# I_O.net
KiCad netlist of a schematic drawn in Altium Designer
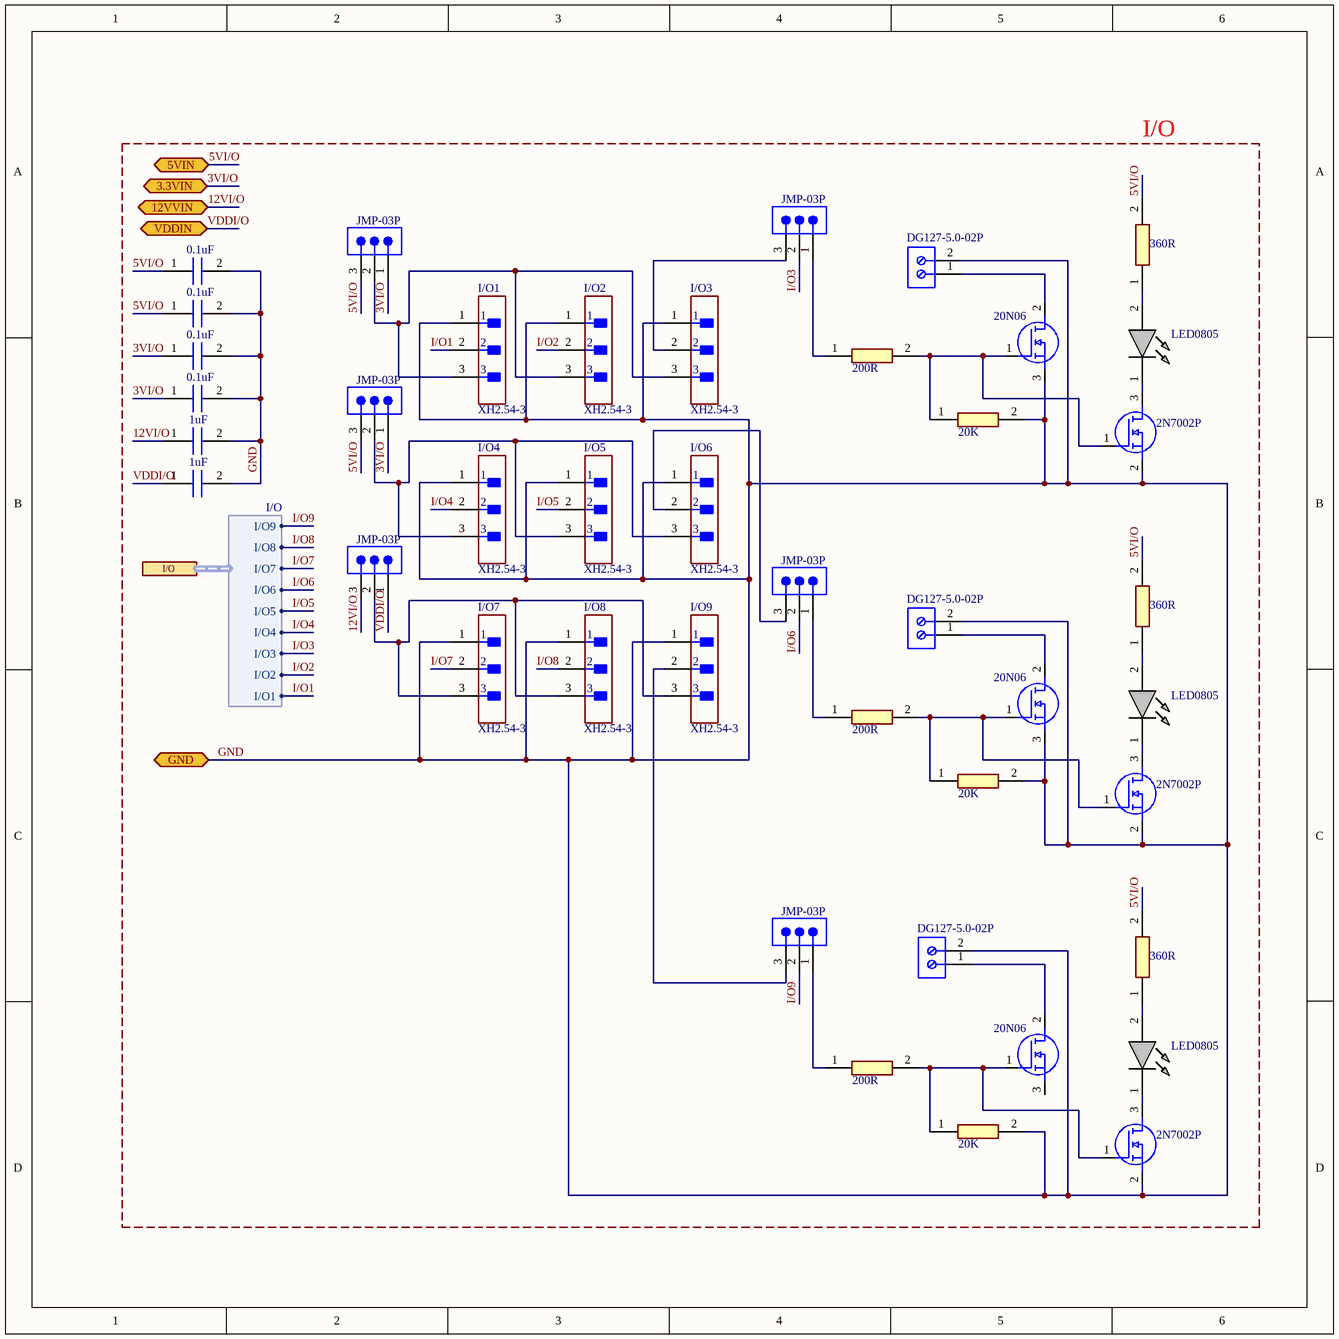
[diagram p0: I_O.SchDoc]

(export (version "E")
  (design (tool "Eeschema 10.0.6"))
  (components
    (comp (ref "CAP3VI/O1")
      (value "0.1uF")
      (footprint "CAP0805")
      (description "CAP-SMD0805")
      (libsource (lib "Components_Robots") (part "CAP0805"))
    )
    (comp (ref "CAP3VI/O2")
      (value "0.1uF")
      (footprint "CAP0805")
      (description "CAP-SMD0805")
      (libsource (lib "Components_Robots") (part "CAP0805"))
    )
    (comp (ref "CAP5VI/O1")
      (value "0.1uF")
      (footprint "CAP0805")
      (description "CAP-SMD0805")
      (libsource (lib "Components_Robots") (part "CAP0805"))
    )
    (comp (ref "CAP5VI/O2")
      (value "0.1uF")
      (footprint "CAP0805")
      (description "CAP-SMD0805")
      (libsource (lib "Components_Robots") (part "CAP0805"))
    )
    (comp (ref "CAP12VI/O")
      (value "1uF")
      (footprint "К10-17Б")
      (description "К10-17Б")
      (libsource (lib "Components_Robots") (part "CAP"))
    )
    (comp (ref "CAPVDDI/O")
      (value "1uF")
      (footprint "К10-17Б")
      (description "К10-17Б")
      (libsource (lib "Components_Robots") (part "CAP"))
    )
    (comp (ref "I/O1")
      (value "XH2.54-3")
      (footprint "XH2.54-3")
      (description "JST XH2.54-3pin")
      (libsource (lib "Components_Robots") (part "XH2.54-3"))
    )
    (comp (ref "I/O2")
      (value "XH2.54-3")
      (footprint "XH2.54-3")
      (description "JST XH2.54-3pin")
      (libsource (lib "Components_Robots") (part "XH2.54-3"))
    )
    (comp (ref "I/O3")
      (value "XH2.54-3")
      (footprint "XH2.54-3")
      (description "JST XH2.54-3pin")
      (libsource (lib "Components_Robots") (part "XH2.54-3"))
    )
    (comp (ref "I/O4")
      (value "XH2.54-3")
      (footprint "XH2.54-3")
      (description "JST XH2.54-3pin")
      (libsource (lib "Components_Robots") (part "XH2.54-3"))
    )
    (comp (ref "I/O5")
      (value "XH2.54-3")
      (footprint "XH2.54-3")
      (description "JST XH2.54-3pin")
      (libsource (lib "Components_Robots") (part "XH2.54-3"))
    )
    (comp (ref "I/O6")
      (value "XH2.54-3")
      (footprint "XH2.54-3")
      (description "JST XH2.54-3pin")
      (libsource (lib "Components_Robots") (part "XH2.54-3"))
    )
    (comp (ref "I/O7")
      (value "XH2.54-3")
      (footprint "XH2.54-3")
      (description "JST XH2.54-3pin")
      (libsource (lib "Components_Robots") (part "XH2.54-3"))
    )
    (comp (ref "I/O8")
      (value "XH2.54-3")
      (footprint "XH2.54-3")
      (description "JST XH2.54-3pin")
      (libsource (lib "Components_Robots") (part "XH2.54-3"))
    )
    (comp (ref "I/O9")
      (value "XH2.54-3")
      (footprint "XH2.54-3")
      (description "JST XH2.54-3pin")
      (libsource (lib "Components_Robots") (part "XH2.54-3"))
    )
    (comp (ref "JMPI/O1")
      (value "JMP-03P")
      (footprint "JMP-03P")
      (description "PLS-1x3")
      (libsource (lib "Components_Robots") (part "JMP-03P"))
    )
    (comp (ref "JMPI/O2")
      (value "JMP-03P")
      (footprint "JMP-03P")
      (description "PLS-1x3")
      (libsource (lib "Components_Robots") (part "JMP-03P"))
    )
    (comp (ref "JMPI/O3")
      (value "JMP-03P")
      (footprint "JMP-03P")
      (description "PLS-1x3")
      (libsource (lib "Components_Robots") (part "JMP-03P"))
    )
    (comp (ref "JMPI/O3HIGH")
      (value "JMP-03P")
      (footprint "JMP-03P")
      (description "PLS-1x3")
      (libsource (lib "Components_Robots") (part "JMP-03P"))
    )
    (comp (ref "JMPI/O6")
      (value "JMP-03P")
      (footprint "JMP-03P")
      (description "PLS-1x3")
      (libsource (lib "Components_Robots") (part "JMP-03P"))
    )
    (comp (ref "JMPI/O9")
      (value "JMP-03P")
      (footprint "JMP-03P")
      (description "PLS-1x3")
      (libsource (lib "Components_Robots") (part "JMP-03P"))
    )
    (comp (ref "LED3(GREEN)")
      (value "LED0805")
      (footprint "LED0805")
      (description "LED-SMD0805")
      (libsource (lib "Components_Robots") (part "LED0805"))
    )
    (comp (ref "LED6(GREEN)")
      (value "LED0805")
      (footprint "LED0805")
      (description "LED-SMD0805")
      (libsource (lib "Components_Robots") (part "LED0805"))
    )
    (comp (ref "LED9(GREEN)")
      (value "LED0805")
      (footprint "LED0805")
      (description "LED-SMD0805")
      (libsource (lib "Components_Robots") (part "LED0805"))
    )
    (comp (ref "M1")
      (value "2N7002P")
      (footprint "2N7002P")
      (description "2N7002P,215")
      (libsource (lib "Components_Robots") (part "2N7002P"))
    )
    (comp (ref "M6")
      (value "2N7002P")
      (footprint "2N7002P")
      (description "2N7002P,215")
      (libsource (lib "Components_Robots") (part "2N7002P"))
    )
    (comp (ref "M9")
      (value "2N7002P")
      (footprint "2N7002P")
      (description "2N7002P,215")
      (libsource (lib "Components_Robots") (part "2N7002P"))
    )
    (comp (ref "MS1")
      (value "20N06")
      (footprint "20N06")
      (description "NMOSFET-20N06")
      (libsource (lib "Components_Robots") (part "20N06"))
    )
    (comp (ref "MS6")
      (value "20N06")
      (footprint "20N06")
      (description "NMOSFET-20N06")
      (libsource (lib "Components_Robots") (part "20N06"))
    )
    (comp (ref "MS9")
      (value "20N06")
      (footprint "20N06")
      (description "NMOSFET-20N06")
      (libsource (lib "Components_Robots") (part "20N06"))
    )
    (comp (ref "OUT3")
      (value "DG127-5.0-02P")
      (footprint "DG127-5.0-02P")
      (description "DG127-5.0-02P-14-00Z")
      (libsource (lib "Components_Robots") (part "DG127-5.0-02P"))
    )
    (comp (ref "OUT6")
      (value "DG127-5.0-02P")
      (footprint "DG127-5.0-02P")
      (description "DG127-5.0-02P-14-00Z")
      (libsource (lib "Components_Robots") (part "DG127-5.0-02P"))
    )
    (comp (ref "OUT9")
      (value "DG127-5.0-02P")
      (footprint "DG127-5.0-02P")
      (description "DG127-5.0-02P-14-00Z")
      (libsource (lib "Components_Robots") (part "DG127-5.0-02P"))
    )
    (comp (ref "RES1")
      (value "200R")
      (footprint "RES0805")
      (description "RES-SMD0805")
      (libsource (lib "Components_Robots") (part "RES0805"))
    )
    (comp (ref "RES2")
      (value "20K")
      (footprint "RES0805")
      (description "RES-SMD0805")
      (libsource (lib "Components_Robots") (part "RES0805"))
    )
    (comp (ref "RES3")
      (value "360R")
      (footprint "RES0805")
      (description "RES-SMD0805")
      (libsource (lib "") (part "RES0805_1"))
    )
    (comp (ref "RES4")
      (value "200R")
      (footprint "RES0805")
      (description "RES-SMD0805")
      (libsource (lib "Components_Robots") (part "RES0805"))
    )
    (comp (ref "RES5")
      (value "20K")
      (footprint "RES0805")
      (description "RES-SMD0805")
      (libsource (lib "Components_Robots") (part "RES0805"))
    )
    (comp (ref "RES6")
      (value "360R")
      (footprint "RES0805")
      (description "RES-SMD0805")
      (libsource (lib "") (part "RES0805_1"))
    )
    (comp (ref "RES7")
      (value "200R")
      (footprint "RES0805")
      (description "RES-SMD0805")
      (libsource (lib "Components_Robots") (part "RES0805"))
    )
    (comp (ref "RES8")
      (value "20K")
      (footprint "RES0805")
      (description "RES-SMD0805")
      (libsource (lib "Components_Robots") (part "RES0805"))
    )
    (comp (ref "RES9")
      (value "360R")
      (footprint "RES0805")
      (description "RES-SMD0805")
      (libsource (lib "") (part "RES0805_1"))
    )
  )
  (nets
    (net (code "2") (name "/3VI{slash}O") (class "Default")
      (node (ref "CAP3VI/O1") (pin "1") (pinfunction "1_1") (pintype "passive"))
      (node (ref "CAP3VI/O2") (pin "1") (pinfunction "1_1") (pintype "passive"))
      (node (ref "JMPI/O1") (pin "1") (pinfunction "1_1") (pintype "passive"))
      (node (ref "JMPI/O2") (pin "1") (pinfunction "1_1") (pintype "passive"))
    )
    (net (code "3") (name "/5VI{slash}O") (class "Default")
      (node (ref "CAP5VI/O1") (pin "1") (pinfunction "1_1") (pintype "passive"))
      (node (ref "CAP5VI/O2") (pin "1") (pinfunction "1_1") (pintype "passive"))
      (node (ref "JMPI/O1") (pin "3") (pinfunction "3_3") (pintype "passive"))
      (node (ref "JMPI/O2") (pin "3") (pinfunction "3_3") (pintype "passive"))
      (node (ref "RES3") (pin "2") (pinfunction "2_2") (pintype "passive"))
      (node (ref "RES6") (pin "2") (pinfunction "2_2") (pintype "passive"))
      (node (ref "RES9") (pin "2") (pinfunction "2_2") (pintype "passive"))
    )
    (net (code "4") (name "/12VI{slash}O") (class "Default")
      (node (ref "CAP12VI/O") (pin "1") (pinfunction "1_1") (pintype "passive"))
      (node (ref "JMPI/O3") (pin "3") (pinfunction "3_3") (pintype "passive"))
    )
    (net (code "5") (name "/GND") (class "Default")
      (node (ref "CAP12VI/O") (pin "2") (pinfunction "2_2") (pintype "passive"))
      (node (ref "CAP3VI/O1") (pin "2") (pinfunction "2_2") (pintype "passive"))
      (node (ref "CAP3VI/O2") (pin "2") (pinfunction "2_2") (pintype "passive"))
      (node (ref "CAP5VI/O1") (pin "2") (pinfunction "2_2") (pintype "passive"))
      (node (ref "CAP5VI/O2") (pin "2") (pinfunction "2_2") (pintype "passive"))
      (node (ref "CAPVDDI/O") (pin "2") (pinfunction "2_2") (pintype "passive"))
      (node (ref "I/O1") (pin "1") (pinfunction "1_1") (pintype "passive"))
      (node (ref "I/O2") (pin "1") (pinfunction "1_1") (pintype "passive"))
      (node (ref "I/O3") (pin "1") (pinfunction "1_1") (pintype "passive"))
      (node (ref "I/O4") (pin "1") (pinfunction "1_1") (pintype "passive"))
      (node (ref "I/O5") (pin "1") (pinfunction "1_1") (pintype "passive"))
      (node (ref "I/O6") (pin "1") (pinfunction "1_1") (pintype "passive"))
      (node (ref "I/O7") (pin "1") (pinfunction "1_1") (pintype "passive"))
      (node (ref "I/O8") (pin "1") (pinfunction "1_1") (pintype "passive"))
      (node (ref "I/O9") (pin "1") (pinfunction "1_1") (pintype "passive"))
      (node (ref "M1") (pin "2") (pinfunction "S_2") (pintype "passive"))
      (node (ref "M6") (pin "2") (pinfunction "S_2") (pintype "passive"))
      (node (ref "M9") (pin "2") (pinfunction "S_2") (pintype "passive"))
      (node (ref "MS1") (pin "3") (pinfunction "S_3") (pintype "passive"))
      (node (ref "MS6") (pin "3") (pinfunction "S_3") (pintype "passive"))
      (node (ref "OUT3") (pin "2") (pinfunction "2_2") (pintype "passive"))
      (node (ref "OUT6") (pin "2") (pinfunction "2_2") (pintype "passive"))
      (node (ref "OUT9") (pin "2") (pinfunction "2_2") (pintype "passive"))
      (node (ref "RES2") (pin "2") (pinfunction "2_2") (pintype "passive"))
      (node (ref "RES5") (pin "2") (pinfunction "2_2") (pintype "passive"))
      (node (ref "RES8") (pin "2") (pinfunction "2_2") (pintype "passive"))
    )
    (net (code "6") (name "/I{slash}O1") (class "Default")
      (node (ref "I/O1") (pin "2") (pinfunction "2_2") (pintype "passive"))
    )
    (net (code "7") (name "/I{slash}O2") (class "Default")
      (node (ref "I/O2") (pin "2") (pinfunction "2_2") (pintype "passive"))
    )
    (net (code "8") (name "/I{slash}O3") (class "Default")
      (node (ref "JMPI/O3HIGH") (pin "2") (pinfunction "2_2") (pintype "passive"))
    )
    (net (code "9") (name "/I{slash}O4") (class "Default")
      (node (ref "I/O4") (pin "2") (pinfunction "2_2") (pintype "passive"))
    )
    (net (code "10") (name "/I{slash}O5") (class "Default")
      (node (ref "I/O5") (pin "2") (pinfunction "2_2") (pintype "passive"))
    )
    (net (code "11") (name "/I{slash}O6") (class "Default")
      (node (ref "JMPI/O6") (pin "2") (pinfunction "2_2") (pintype "passive"))
    )
    (net (code "12") (name "/I{slash}O7") (class "Default")
      (node (ref "I/O7") (pin "2") (pinfunction "2_2") (pintype "passive"))
    )
    (net (code "13") (name "/I{slash}O8") (class "Default")
      (node (ref "I/O8") (pin "2") (pinfunction "2_2") (pintype "passive"))
    )
    (net (code "14") (name "/I{slash}O9") (class "Default")
      (node (ref "JMPI/O9") (pin "2") (pinfunction "2_2") (pintype "passive"))
    )
    (net (code "15") (name "/VDDI{slash}O") (class "Default")
      (node (ref "CAPVDDI/O") (pin "1") (pinfunction "1_1") (pintype "passive"))
      (node (ref "JMPI/O3") (pin "1") (pinfunction "1_1") (pintype "passive"))
    )
    (net (code "17") (name "Net-(I/O1-Pad3)") (class "Default")
      (node (ref "I/O1") (pin "3") (pinfunction "3_3") (pintype "passive"))
      (node (ref "I/O2") (pin "3") (pinfunction "3_3") (pintype "passive"))
      (node (ref "I/O3") (pin "3") (pinfunction "3_3") (pintype "passive"))
      (node (ref "JMPI/O1") (pin "2") (pinfunction "2_2") (pintype "passive"))
    )
    (net (code "18") (name "Net-(I/O3-Pad2)") (class "Default")
      (node (ref "I/O3") (pin "2") (pinfunction "2_2") (pintype "passive"))
      (node (ref "JMPI/O3HIGH") (pin "3") (pinfunction "3_3") (pintype "passive"))
    )
    (net (code "19") (name "Net-(I/O4-Pad3)") (class "Default")
      (node (ref "I/O4") (pin "3") (pinfunction "3_3") (pintype "passive"))
      (node (ref "I/O5") (pin "3") (pinfunction "3_3") (pintype "passive"))
      (node (ref "I/O6") (pin "3") (pinfunction "3_3") (pintype "passive"))
      (node (ref "JMPI/O2") (pin "2") (pinfunction "2_2") (pintype "passive"))
    )
    (net (code "20") (name "Net-(I/O6-Pad2)") (class "Default")
      (node (ref "I/O6") (pin "2") (pinfunction "2_2") (pintype "passive"))
      (node (ref "JMPI/O6") (pin "3") (pinfunction "3_3") (pintype "passive"))
    )
    (net (code "21") (name "Net-(I/O7-Pad3)") (class "Default")
      (node (ref "I/O7") (pin "3") (pinfunction "3_3") (pintype "passive"))
      (node (ref "I/O8") (pin "3") (pinfunction "3_3") (pintype "passive"))
      (node (ref "I/O9") (pin "3") (pinfunction "3_3") (pintype "passive"))
      (node (ref "JMPI/O3") (pin "2") (pinfunction "2_2") (pintype "passive"))
    )
    (net (code "22") (name "Net-(I/O9-Pad2)") (class "Default")
      (node (ref "I/O9") (pin "2") (pinfunction "2_2") (pintype "passive"))
      (node (ref "JMPI/O9") (pin "3") (pinfunction "3_3") (pintype "passive"))
    )
    (net (code "23") (name "Net-(JMPI/O3HIGH-Pad1)") (class "Default")
      (node (ref "JMPI/O3HIGH") (pin "1") (pinfunction "1_1") (pintype "passive"))
      (node (ref "RES1") (pin "1") (pinfunction "1_1") (pintype "passive"))
    )
    (net (code "24") (name "Net-(JMPI/O6-Pad1)") (class "Default")
      (node (ref "JMPI/O6") (pin "1") (pinfunction "1_1") (pintype "passive"))
      (node (ref "RES4") (pin "1") (pinfunction "1_1") (pintype "passive"))
    )
    (net (code "25") (name "Net-(JMPI/O9-Pad1)") (class "Default")
      (node (ref "JMPI/O9") (pin "1") (pinfunction "1_1") (pintype "passive"))
      (node (ref "RES7") (pin "1") (pinfunction "1_1") (pintype "passive"))
    )
    (net (code "26") (name "Net-(LED3(GREEN)-A)") (class "Default")
      (node (ref "LED3(GREEN)") (pin "2") (pinfunction "A_2") (pintype "passive"))
      (node (ref "RES3") (pin "1") (pinfunction "1_1") (pintype "passive"))
    )
    (net (code "27") (name "Net-(LED3(GREEN)-K)") (class "Default")
      (node (ref "LED3(GREEN)") (pin "1") (pinfunction "K_1") (pintype "passive"))
      (node (ref "M1") (pin "3") (pinfunction "D_3") (pintype "passive"))
    )
    (net (code "28") (name "Net-(LED6(GREEN)-A)") (class "Default")
      (node (ref "LED6(GREEN)") (pin "2") (pinfunction "A_2") (pintype "passive"))
      (node (ref "RES6") (pin "1") (pinfunction "1_1") (pintype "passive"))
    )
    (net (code "29") (name "Net-(LED6(GREEN)-K)") (class "Default")
      (node (ref "LED6(GREEN)") (pin "1") (pinfunction "K_1") (pintype "passive"))
      (node (ref "M6") (pin "3") (pinfunction "D_3") (pintype "passive"))
    )
    (net (code "30") (name "Net-(LED9(GREEN)-A)") (class "Default")
      (node (ref "LED9(GREEN)") (pin "2") (pinfunction "A_2") (pintype "passive"))
      (node (ref "RES9") (pin "1") (pinfunction "1_1") (pintype "passive"))
    )
    (net (code "31") (name "Net-(LED9(GREEN)-K)") (class "Default")
      (node (ref "LED9(GREEN)") (pin "1") (pinfunction "K_1") (pintype "passive"))
      (node (ref "M9") (pin "3") (pinfunction "D_3") (pintype "passive"))
    )
    (net (code "32") (name "Net-(M1-G)") (class "Default")
      (node (ref "M1") (pin "1") (pinfunction "G_1") (pintype "passive"))
      (node (ref "MS1") (pin "1") (pinfunction "G_1") (pintype "passive"))
      (node (ref "RES1") (pin "2") (pinfunction "2_2") (pintype "passive"))
      (node (ref "RES2") (pin "1") (pinfunction "1_1") (pintype "passive"))
    )
    (net (code "33") (name "Net-(M6-G)") (class "Default")
      (node (ref "M6") (pin "1") (pinfunction "G_1") (pintype "passive"))
      (node (ref "MS6") (pin "1") (pinfunction "G_1") (pintype "passive"))
      (node (ref "RES4") (pin "2") (pinfunction "2_2") (pintype "passive"))
      (node (ref "RES5") (pin "1") (pinfunction "1_1") (pintype "passive"))
    )
    (net (code "34") (name "Net-(M9-G)") (class "Default")
      (node (ref "M9") (pin "1") (pinfunction "G_1") (pintype "passive"))
      (node (ref "MS9") (pin "1") (pinfunction "G_1") (pintype "passive"))
      (node (ref "RES7") (pin "2") (pinfunction "2_2") (pintype "passive"))
      (node (ref "RES8") (pin "1") (pinfunction "1_1") (pintype "passive"))
    )
    (net (code "35") (name "Net-(MS1-D)") (class "Default")
      (node (ref "MS1") (pin "2") (pinfunction "D_2") (pintype "passive"))
      (node (ref "OUT3") (pin "1") (pinfunction "1_1") (pintype "passive"))
    )
    (net (code "36") (name "Net-(MS6-D)") (class "Default")
      (node (ref "MS6") (pin "2") (pinfunction "D_2") (pintype "passive"))
      (node (ref "OUT6") (pin "1") (pinfunction "1_1") (pintype "passive"))
    )
    (net (code "37") (name "Net-(MS9-D)") (class "Default")
      (node (ref "MS9") (pin "2") (pinfunction "D_2") (pintype "passive"))
      (node (ref "OUT9") (pin "1") (pinfunction "1_1") (pintype "passive"))
    )
    (net (code "38") (name "unconnected-(MS9-S-Pad3)") (class "Default")
      (node (ref "MS9") (pin "3") (pinfunction "S_3") (pintype "passive"))
    )
  )
)
